# workshopelectro.net
KiCad netlist of a schematic drawn in EAGLE
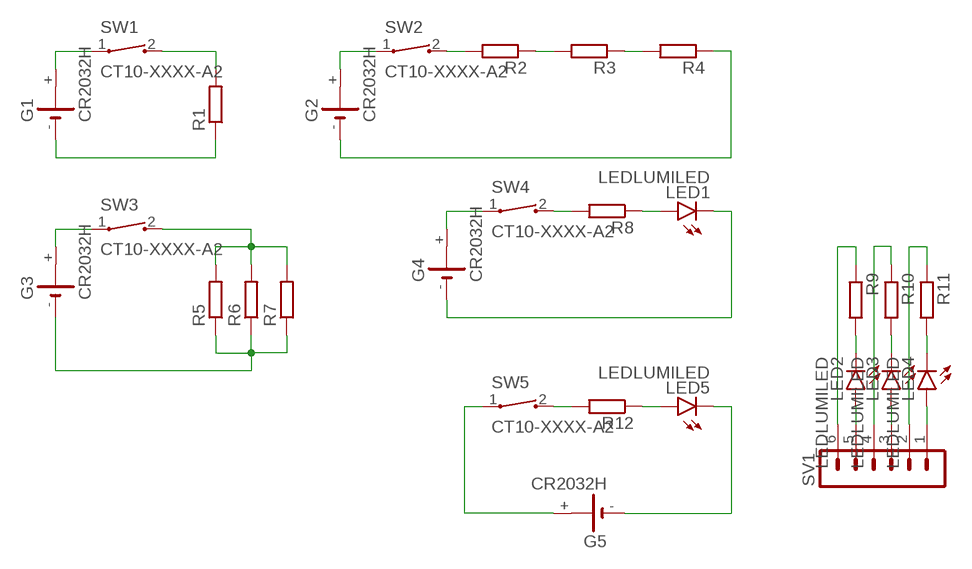
[diagram p0: schematic, sheet 1]

(export (version "E")
  (design (tool "Eeschema 10.0.6"))
  (components
    (comp (ref "G1")
      (value "CR2032H")
      (footprint "eagle-import:CR2032H")
      (libsource (lib "eagle-import") (part "CR2032H"))
    )
    (comp (ref "G2")
      (value "CR2032H")
      (footprint "eagle-import:CR2032H")
      (libsource (lib "eagle-import") (part "CR2032H"))
    )
    (comp (ref "G3")
      (value "CR2032H")
      (footprint "eagle-import:CR2032H")
      (libsource (lib "eagle-import") (part "CR2032H"))
    )
    (comp (ref "G4")
      (value "CR2032H")
      (footprint "eagle-import:CR2032H")
      (libsource (lib "eagle-import") (part "CR2032H"))
    )
    (comp (ref "G5")
      (value "CR2032H")
      (footprint "eagle-import:CR2032H")
      (libsource (lib "eagle-import") (part "CR2032H"))
    )
    (comp (ref "LED1")
      (value "LEDLUMILED")
      (footprint "eagle-import:LUMILED")
      (libsource (lib "eagle-import") (part "LEDLUMILED"))
    )
    (comp (ref "LED2")
      (value "LEDLUMILED")
      (footprint "eagle-import:LUMILED")
      (libsource (lib "eagle-import") (part "LEDLUMILED"))
    )
    (comp (ref "LED3")
      (value "LEDLUMILED")
      (footprint "eagle-import:LUMILED")
      (libsource (lib "eagle-import") (part "LEDLUMILED"))
    )
    (comp (ref "LED4")
      (value "LEDLUMILED")
      (footprint "eagle-import:LUMILED")
      (libsource (lib "eagle-import") (part "LEDLUMILED"))
    )
    (comp (ref "LED5")
      (value "LEDLUMILED")
      (footprint "eagle-import:LUMILED")
      (libsource (lib "eagle-import") (part "LEDLUMILED"))
    )
    (comp (ref "R1")
      (value "R-EU_0204/2V")
      (footprint "eagle-import:0204V")
      (libsource (lib "eagle-import") (part "R-EU_0204/2V"))
    )
    (comp (ref "R2")
      (value "R-EU_0204/2V")
      (footprint "eagle-import:0204V")
      (libsource (lib "eagle-import") (part "R-EU_0204/2V"))
    )
    (comp (ref "R3")
      (value "R-EU_0204/2V")
      (footprint "eagle-import:0204V")
      (libsource (lib "eagle-import") (part "R-EU_0204/2V"))
    )
    (comp (ref "R4")
      (value "R-EU_0204/2V")
      (footprint "eagle-import:0204V")
      (libsource (lib "eagle-import") (part "R-EU_0204/2V"))
    )
    (comp (ref "R5")
      (value "R-EU_0204/2V")
      (footprint "eagle-import:0204V")
      (libsource (lib "eagle-import") (part "R-EU_0204/2V"))
    )
    (comp (ref "R6")
      (value "R-EU_0204/2V")
      (footprint "eagle-import:0204V")
      (libsource (lib "eagle-import") (part "R-EU_0204/2V"))
    )
    (comp (ref "R7")
      (value "R-EU_0204/2V")
      (footprint "eagle-import:0204V")
      (libsource (lib "eagle-import") (part "R-EU_0204/2V"))
    )
    (comp (ref "R8")
      (value "R-EU_0204/2V")
      (footprint "eagle-import:0204V")
      (libsource (lib "eagle-import") (part "R-EU_0204/2V"))
    )
    (comp (ref "R9")
      (value "R-EU_0204/2V")
      (footprint "eagle-import:0204V")
      (libsource (lib "eagle-import") (part "R-EU_0204/2V"))
    )
    (comp (ref "R10")
      (value "R-EU_0204/2V")
      (footprint "eagle-import:0204V")
      (libsource (lib "eagle-import") (part "R-EU_0204/2V"))
    )
    (comp (ref "R11")
      (value "R-EU_0204/2V")
      (footprint "eagle-import:0204V")
      (libsource (lib "eagle-import") (part "R-EU_0204/2V"))
    )
    (comp (ref "R12")
      (value "R-EU_0204/2V")
      (footprint "eagle-import:0204V")
      (libsource (lib "eagle-import") (part "R-EU_0204/2V"))
    )
    (comp (ref "SV1")
      (value "MA06-1")
      (footprint "eagle-import:MA06-1")
      (libsource (lib "eagle-import") (part "MA06-1"))
    )
    (comp (ref "SW1")
      (value "CT10-XXXX-A2")
      (footprint "eagle-import:CT10-XXXX-A2")
      (libsource (lib "eagle-import") (part "CT10-XXXX-A2"))
    )
    (comp (ref "SW2")
      (value "CT10-XXXX-A2")
      (footprint "eagle-import:CT10-XXXX-A2")
      (libsource (lib "eagle-import") (part "CT10-XXXX-A2"))
    )
    (comp (ref "SW3")
      (value "CT10-XXXX-A2")
      (footprint "eagle-import:CT10-XXXX-A2")
      (libsource (lib "eagle-import") (part "CT10-XXXX-A2"))
    )
    (comp (ref "SW4")
      (value "CT10-XXXX-A2")
      (footprint "eagle-import:CT10-XXXX-A2")
      (libsource (lib "eagle-import") (part "CT10-XXXX-A2"))
    )
    (comp (ref "SW5")
      (value "CT10-XXXX-A2")
      (footprint "eagle-import:CT10-XXXX-A2")
      (libsource (lib "eagle-import") (part "CT10-XXXX-A2"))
    )
  )
  (nets
    (net (code "1") (name "Net-(G1-Pad+)") (class "Default")
      (node (ref "G1") (pin "+") (pinfunction "+_+") (pintype "passive"))
      (node (ref "SW1") (pin "1") (pinfunction "1_1") (pintype "passive"))
    )
    (net (code "2") (name "Net-(G1-Pad-)") (class "Default")
      (node (ref "G1") (pin "-") (pinfunction "-_-") (pintype "passive"))
      (node (ref "R1") (pin "1") (pinfunction "1_1") (pintype "passive"))
    )
    (net (code "3") (name "Net-(G2-Pad+)") (class "Default")
      (node (ref "G2") (pin "+") (pinfunction "+_+") (pintype "passive"))
      (node (ref "SW2") (pin "1") (pinfunction "1_1") (pintype "passive"))
    )
    (net (code "4") (name "Net-(G2-Pad-)") (class "Default")
      (node (ref "G2") (pin "-") (pinfunction "-_-") (pintype "passive"))
      (node (ref "R4") (pin "1") (pinfunction "1_1") (pintype "passive"))
    )
    (net (code "5") (name "Net-(G3-Pad+)") (class "Default")
      (node (ref "G3") (pin "+") (pinfunction "+_+") (pintype "passive"))
      (node (ref "SW3") (pin "1") (pinfunction "1_1") (pintype "passive"))
    )
    (net (code "6") (name "Net-(G3-Pad-)") (class "Default")
      (node (ref "G3") (pin "-") (pinfunction "-_-") (pintype "passive"))
      (node (ref "R5") (pin "1") (pinfunction "1_1") (pintype "passive"))
      (node (ref "R6") (pin "1") (pinfunction "1_1") (pintype "passive"))
      (node (ref "R7") (pin "1") (pinfunction "1_1") (pintype "passive"))
    )
    (net (code "7") (name "Net-(G4-Pad+)") (class "Default")
      (node (ref "G4") (pin "+") (pinfunction "+_+") (pintype "passive"))
      (node (ref "SW4") (pin "1") (pinfunction "1_1") (pintype "passive"))
    )
    (net (code "8") (name "Net-(G5-Pad+)") (class "Default")
      (node (ref "G5") (pin "+") (pinfunction "+_+") (pintype "passive"))
      (node (ref "SW5") (pin "1") (pinfunction "1_1") (pintype "passive"))
    )
    (net (code "9") (name "Net-(LED1-A)") (class "Default")
      (node (ref "LED1") (pin "2+") (pinfunction "A_2+") (pintype "passive"))
      (node (ref "R8") (pin "1") (pinfunction "1_1") (pintype "passive"))
    )
    (net (code "10") (name "Net-(LED1-C)") (class "Default")
      (node (ref "G4") (pin "-") (pinfunction "-_-") (pintype "passive"))
      (node (ref "LED1") (pin "4-") (pinfunction "C_4-") (pintype "passive"))
    )
    (net (code "11") (name "Net-(LED2-A)") (class "Default")
      (node (ref "LED2") (pin "2+") (pinfunction "A_2+") (pintype "passive"))
      (node (ref "SV1") (pin "5") (pinfunction "5_5") (pintype "passive"))
    )
    (net (code "12") (name "Net-(LED2-C)") (class "Default")
      (node (ref "LED2") (pin "4-") (pinfunction "C_4-") (pintype "passive"))
      (node (ref "R9") (pin "2") (pinfunction "2_2") (pintype "passive"))
    )
    (net (code "13") (name "Net-(LED3-A)") (class "Default")
      (node (ref "LED3") (pin "2+") (pinfunction "A_2+") (pintype "passive"))
      (node (ref "SV1") (pin "3") (pinfunction "3_3") (pintype "passive"))
    )
    (net (code "14") (name "Net-(LED3-C)") (class "Default")
      (node (ref "LED3") (pin "4-") (pinfunction "C_4-") (pintype "passive"))
      (node (ref "R10") (pin "2") (pinfunction "2_2") (pintype "passive"))
    )
    (net (code "15") (name "Net-(LED4-A)") (class "Default")
      (node (ref "LED4") (pin "2+") (pinfunction "A_2+") (pintype "passive"))
      (node (ref "SV1") (pin "1") (pinfunction "1_1") (pintype "passive"))
    )
    (net (code "16") (name "Net-(LED4-C)") (class "Default")
      (node (ref "LED4") (pin "4-") (pinfunction "C_4-") (pintype "passive"))
      (node (ref "R11") (pin "2") (pinfunction "2_2") (pintype "passive"))
    )
    (net (code "17") (name "Net-(LED5-A)") (class "Default")
      (node (ref "LED5") (pin "2+") (pinfunction "A_2+") (pintype "passive"))
      (node (ref "R12") (pin "1") (pinfunction "1_1") (pintype "passive"))
    )
    (net (code "18") (name "Net-(LED5-C)") (class "Default")
      (node (ref "G5") (pin "-") (pinfunction "-_-") (pintype "passive"))
      (node (ref "LED5") (pin "4-") (pinfunction "C_4-") (pintype "passive"))
    )
    (net (code "19") (name "Net-(R1-Pad2)") (class "Default")
      (node (ref "R1") (pin "2") (pinfunction "2_2") (pintype "passive"))
      (node (ref "SW1") (pin "2") (pinfunction "2_2") (pintype "passive"))
    )
    (net (code "20") (name "Net-(R2-Pad1)") (class "Default")
      (node (ref "R2") (pin "1") (pinfunction "1_1") (pintype "passive"))
      (node (ref "R3") (pin "2") (pinfunction "2_2") (pintype "passive"))
    )
    (net (code "21") (name "Net-(R2-Pad2)") (class "Default")
      (node (ref "R2") (pin "2") (pinfunction "2_2") (pintype "passive"))
      (node (ref "SW2") (pin "2") (pinfunction "2_2") (pintype "passive"))
    )
    (net (code "22") (name "Net-(R3-Pad1)") (class "Default")
      (node (ref "R3") (pin "1") (pinfunction "1_1") (pintype "passive"))
      (node (ref "R4") (pin "2") (pinfunction "2_2") (pintype "passive"))
    )
    (net (code "23") (name "Net-(R5-Pad2)") (class "Default")
      (node (ref "R5") (pin "2") (pinfunction "2_2") (pintype "passive"))
      (node (ref "R6") (pin "2") (pinfunction "2_2") (pintype "passive"))
      (node (ref "R7") (pin "2") (pinfunction "2_2") (pintype "passive"))
      (node (ref "SW3") (pin "2") (pinfunction "2_2") (pintype "passive"))
    )
    (net (code "24") (name "Net-(R8-Pad2)") (class "Default")
      (node (ref "R8") (pin "2") (pinfunction "2_2") (pintype "passive"))
      (node (ref "SW4") (pin "2") (pinfunction "2_2") (pintype "passive"))
    )
    (net (code "25") (name "Net-(R9-Pad1)") (class "Default")
      (node (ref "R9") (pin "1") (pinfunction "1_1") (pintype "passive"))
      (node (ref "SV1") (pin "6") (pinfunction "6_6") (pintype "passive"))
    )
    (net (code "26") (name "Net-(R10-Pad1)") (class "Default")
      (node (ref "R10") (pin "1") (pinfunction "1_1") (pintype "passive"))
      (node (ref "SV1") (pin "4") (pinfunction "4_4") (pintype "passive"))
    )
    (net (code "27") (name "Net-(R11-Pad1)") (class "Default")
      (node (ref "R11") (pin "1") (pinfunction "1_1") (pintype "passive"))
      (node (ref "SV1") (pin "2") (pinfunction "2_2") (pintype "passive"))
    )
    (net (code "28") (name "Net-(R12-Pad2)") (class "Default")
      (node (ref "R12") (pin "2") (pinfunction "2_2") (pintype "passive"))
      (node (ref "SW5") (pin "2") (pinfunction "2_2") (pintype "passive"))
    )
    (net (code "29") (name "unconnected-(G1-+-Pad+@1)") (class "Default")
      (node (ref "G1") (pin "+@1") (pinfunction "+_+@1") (pintype "passive"))
    )
    (net (code "30") (name "unconnected-(G2-+-Pad+@1)") (class "Default")
      (node (ref "G2") (pin "+@1") (pinfunction "+_+@1") (pintype "passive"))
    )
    (net (code "31") (name "unconnected-(G3-+-Pad+@1)") (class "Default")
      (node (ref "G3") (pin "+@1") (pinfunction "+_+@1") (pintype "passive"))
    )
    (net (code "32") (name "unconnected-(G4-+-Pad+@1)") (class "Default")
      (node (ref "G4") (pin "+@1") (pinfunction "+_+@1") (pintype "passive"))
    )
    (net (code "33") (name "unconnected-(G5-+-Pad+@1)") (class "Default")
      (node (ref "G5") (pin "+@1") (pinfunction "+_+@1") (pintype "passive"))
    )
  )
)
